# openmv.net
KiCad netlist of a schematic drawn in EAGLE
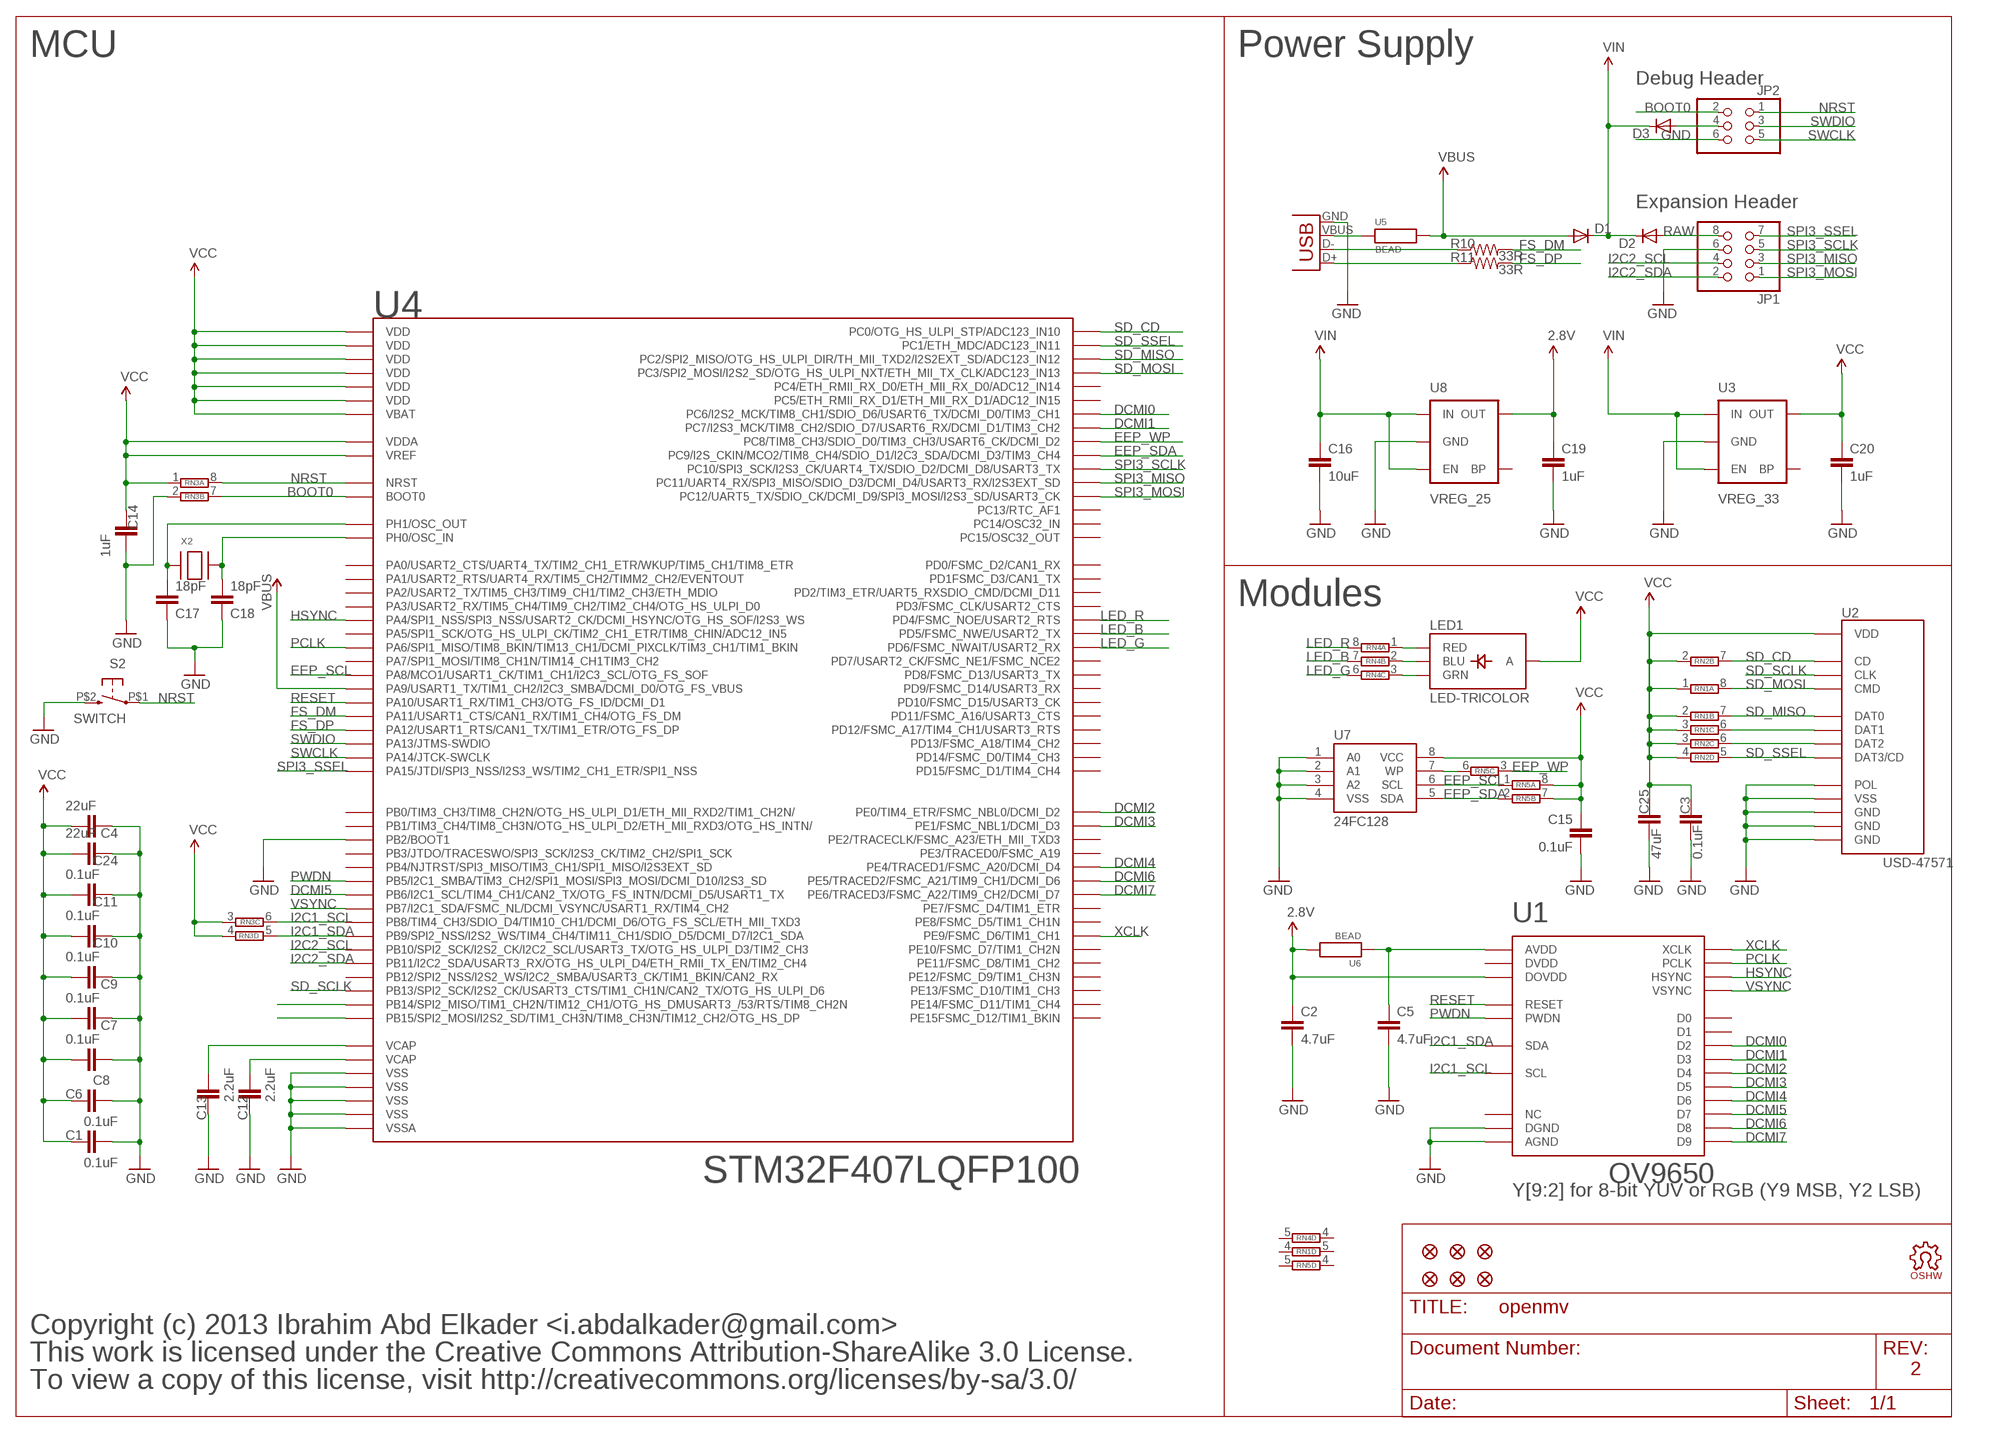
[diagram p0: schematic, sheet 1]

(export (version "E")
  (design (tool "Eeschema 10.0.6"))
  (components
    (comp (ref "C1")
      (value "0.1uF")
      (footprint "eagle-import:0402-CAP")
      (libsource (lib "eagle-import") (part "CAP0402-CAP"))
    )
    (comp (ref "C2")
      (value "4.7uF")
      (footprint "eagle-import:0402-CAP")
      (libsource (lib "eagle-import") (part "CAP0402-CAP"))
    )
    (comp (ref "C3")
      (value "0.1uF")
      (footprint "eagle-import:0402-CAP")
      (libsource (lib "eagle-import") (part "CAP0402-CAP"))
    )
    (comp (ref "C4")
      (value "22uF")
      (footprint "eagle-import:0805")
      (libsource (lib "eagle-import") (part "CAP0805"))
    )
    (comp (ref "C5")
      (value "4.7uF")
      (footprint "eagle-import:0402-CAP")
      (libsource (lib "eagle-import") (part "CAP0402-CAP"))
    )
    (comp (ref "C6")
      (value "0.1uF")
      (footprint "eagle-import:0402-CAP")
      (libsource (lib "eagle-import") (part "CAP0402-CAP"))
    )
    (comp (ref "C7")
      (value "0.1uF")
      (footprint "eagle-import:0402-CAP")
      (libsource (lib "eagle-import") (part "CAP0402-CAP"))
    )
    (comp (ref "C8")
      (value "0.1uF")
      (footprint "eagle-import:0402-CAP")
      (libsource (lib "eagle-import") (part "CAP0402-CAP"))
    )
    (comp (ref "C9")
      (value "0.1uF")
      (footprint "eagle-import:0402-CAP")
      (libsource (lib "eagle-import") (part "CAP0402-CAP"))
    )
    (comp (ref "C10")
      (value "0.1uF")
      (footprint "eagle-import:0402-CAP")
      (libsource (lib "eagle-import") (part "CAP0402-CAP"))
    )
    (comp (ref "C11")
      (value "0.1uF")
      (footprint "eagle-import:0402-CAP")
      (libsource (lib "eagle-import") (part "CAP0402-CAP"))
    )
    (comp (ref "C12")
      (value "2.2uF")
      (footprint "eagle-import:0402-CAP")
      (libsource (lib "eagle-import") (part "CAP0402-CAP"))
    )
    (comp (ref "C13")
      (value "2.2uF")
      (footprint "eagle-import:0402-CAP")
      (libsource (lib "eagle-import") (part "CAP0402-CAP"))
    )
    (comp (ref "C14")
      (value "1uF")
      (footprint "eagle-import:0402-CAP")
      (libsource (lib "eagle-import") (part "CAP0402-CAP"))
    )
    (comp (ref "C15")
      (value "0.1uF")
      (footprint "eagle-import:0402-CAP")
      (libsource (lib "eagle-import") (part "CAP0402-CAP"))
    )
    (comp (ref "C16")
      (value "10uF")
      (footprint "eagle-import:0805")
      (libsource (lib "eagle-import") (part "CAP0805"))
    )
    (comp (ref "C17")
      (value "18pF")
      (footprint "eagle-import:0402-CAP")
      (libsource (lib "eagle-import") (part "CAP0402-CAP"))
    )
    (comp (ref "C18")
      (value "18pF")
      (footprint "eagle-import:0402-CAP")
      (libsource (lib "eagle-import") (part "CAP0402-CAP"))
    )
    (comp (ref "C19")
      (value "1uF")
      (footprint "eagle-import:0402-CAP")
      (libsource (lib "eagle-import") (part "CAP0402-CAP"))
    )
    (comp (ref "C20")
      (value "1uF")
      (footprint "eagle-import:0402-CAP")
      (libsource (lib "eagle-import") (part "CAP0402-CAP"))
    )
    (comp (ref "C24")
      (value "22uF")
      (footprint "eagle-import:0805")
      (libsource (lib "eagle-import") (part "CAP0805"))
    )
    (comp (ref "C25")
      (value "47uF")
      (footprint "eagle-import:0805")
      (libsource (lib "eagle-import") (part "CAP0805"))
    )
    (comp (ref "D1")
      (value "DIODESOD")
      (footprint "eagle-import:SOD-323")
      (libsource (lib "eagle-import") (part "DIODESOD"))
    )
    (comp (ref "D2")
      (value "DIODESOD")
      (footprint "eagle-import:SOD-323")
      (libsource (lib "eagle-import") (part "DIODESOD"))
    )
    (comp (ref "D3")
      (value "DIODESOD")
      (footprint "eagle-import:SOD-323")
      (libsource (lib "eagle-import") (part "DIODESOD"))
    )
    (comp (ref "JP1")
      (value "PINHD-2X4")
      (footprint "eagle-import:2X04")
      (libsource (lib "eagle-import") (part "PINHD-2X4"))
    )
    (comp (ref "JP2")
      (value "PINHD-2X3")
      (footprint "eagle-import:2X03")
      (libsource (lib "eagle-import") (part "PINHD-2X3"))
    )
    (comp (ref "JP3")
      (value "FIDUCIAL1X2")
      (footprint "eagle-import:FIDUCIAL-1X2")
      (libsource (lib "eagle-import") (part "FIDUCIAL1X2"))
    )
    (comp (ref "JP4")
      (value "FIDUCIAL1X2")
      (footprint "eagle-import:FIDUCIAL-1X2")
      (libsource (lib "eagle-import") (part "FIDUCIAL1X2"))
    )
    (comp (ref "JP5")
      (value "FIDUCIAL1X2")
      (footprint "eagle-import:FIDUCIAL-1X2")
      (libsource (lib "eagle-import") (part "FIDUCIAL1X2"))
    )
    (comp (ref "JP6")
      (value "FIDUCIAL1X2")
      (footprint "eagle-import:FIDUCIAL-1X2")
      (libsource (lib "eagle-import") (part "FIDUCIAL1X2"))
    )
    (comp (ref "JP7")
      (value "FIDUCIAL1X2")
      (footprint "eagle-import:FIDUCIAL-1X2")
      (libsource (lib "eagle-import") (part "FIDUCIAL1X2"))
    )
    (comp (ref "JP8")
      (value "FIDUCIAL1X2")
      (footprint "eagle-import:FIDUCIAL-1X2")
      (libsource (lib "eagle-import") (part "FIDUCIAL1X2"))
    )
    (comp (ref "LED1")
      (value "LED-TRICOLOR")
      (footprint "eagle-import:LED-TRICOLOR-SMD")
      (libsource (lib "eagle-import") (part "LED-TRICOLOR"))
    )
    (comp (ref "LOGO1")
      (value "OSHW_LOGO_FILLX0150-NT")
      (footprint "eagle-import:OSHW_FILLX150_NOTEXT")
      (libsource (lib "eagle-import") (part "OSHW_LOGO_FILLX0150-NT"))
    )
    (comp (ref "R10")
      (value "33R")
      (footprint "eagle-import:0402-RES")
      (libsource (lib "eagle-import") (part "RESISTOR0402-RES"))
    )
    (comp (ref "R11")
      (value "33R")
      (footprint "eagle-import:0402-RES")
      (libsource (lib "eagle-import") (part "RESISTOR0402-RES"))
    )
    (comp (ref "RN1")
      (value "4R-NCAT16")
      (footprint "eagle-import:CAT16")
      (fields (field (name "OC_FARNELL") "unknown") (field (name "OC_NEWARK") "unknown"))
      (libsource (lib "eagle-import") (part "4R-NCAT16"))
    )
    (comp (ref "RN2")
      (value "4R-NCAT16")
      (footprint "eagle-import:CAT16")
      (fields (field (name "OC_FARNELL") "unknown") (field (name "OC_NEWARK") "unknown"))
      (libsource (lib "eagle-import") (part "4R-NCAT16"))
    )
    (comp (ref "RN3")
      (value "4R-NCAT16")
      (footprint "eagle-import:CAT16")
      (libsource (lib "eagle-import") (part "4R-NCAT16"))
    )
    (comp (ref "RN4")
      (value "4R-NCAT16")
      (footprint "eagle-import:CAT16")
      (fields (field (name "OC_FARNELL") "unknown") (field (name "OC_NEWARK") "unknown"))
      (libsource (lib "eagle-import") (part "4R-NCAT16"))
    )
    (comp (ref "RN5")
      (value "4R-NCAT16")
      (footprint "eagle-import:CAT16")
      (fields (field (name "OC_FARNELL") "unknown") (field (name "OC_NEWARK") "unknown"))
      (libsource (lib "eagle-import") (part "4R-NCAT16"))
    )
    (comp (ref "S2")
      (value "SWITCH")
      (footprint "eagle-import:B3U-1000P")
      (libsource (lib "eagle-import") (part "SWITCH"))
    )
    (comp (ref "U1")
      (value "OV9650")
      (footprint "eagle-import:OV9650")
      (libsource (lib "eagle-import") (part "OV9650"))
    )
    (comp (ref "U2")
      (value "USD-47571")
      (footprint "eagle-import:USD-47571")
      (libsource (lib "eagle-import") (part "USD-47571"))
    )
    (comp (ref "U3")
      (value "VREG_33")
      (footprint "eagle-import:SOT23-5")
      (libsource (lib "eagle-import") (part "V_REG_LDOSMD"))
    )
    (comp (ref "U4")
      (value "STM32F407LQFP100")
      (footprint "eagle-import:LQFP100")
      (libsource (lib "eagle-import") (part "STM32F407LQFP100"))
    )
    (comp (ref "U5")
      (value "BEAD")
      (footprint "eagle-import:0402-CAP")
      (libsource (lib "eagle-import") (part "BEAD"))
    )
    (comp (ref "U6")
      (value "BEAD")
      (footprint "eagle-import:0402-CAP")
      (libsource (lib "eagle-import") (part "BEAD"))
    )
    (comp (ref "U7")
      (value "24FC128")
      (footprint "eagle-import:MSOP8")
      (libsource (lib "eagle-import") (part "24FC128"))
    )
    (comp (ref "U8")
      (value "VREG_25")
      (footprint "eagle-import:SOT23-5")
      (libsource (lib "eagle-import") (part "V_REG_LDOSMD"))
    )
    (comp (ref "X1")
      (value "USB-MICROB")
      (footprint "eagle-import:USB-MICROB")
      (libsource (lib "eagle-import") (part "USB-MICROB"))
    )
    (comp (ref "X2")
      (value "XTALNX5032")
      (footprint "eagle-import:NX5032")
      (libsource (lib "eagle-import") (part "XTALNX5032"))
    )
  )
  (nets
    (net (code "1") (name "/BOOT0") (class "Default")
      (node (ref "JP2") (pin "2") (pinfunction "2_2") (pintype "passive"))
      (node (ref "RN3") (pin "7") (pinfunction "2_7") (pintype "passive"))
      (node (ref "U4") (pin "94") (pinfunction "BOOT0_94") (pintype "bidirectional"))
    )
    (net (code "2") (name "/DCMI0") (class "Default")
      (node (ref "U1") (pin "P$19") (pinfunction "D2_P$19") (pintype "bidirectional"))
      (node (ref "U4") (pin "63") (pinfunction "PC6/I2S2_MCK/TIM8_CH1/SDIO_D6/USART6_TX/DCMI_D0/TIM3_CH1_63") (pintype "bidirectional"))
    )
    (net (code "3") (name "/DCMI1") (class "Default")
      (node (ref "U1") (pin "P$21") (pinfunction "D3_P$21") (pintype "bidirectional"))
      (node (ref "U4") (pin "64") (pinfunction "PC7/I2S3_MCK/TIM8_CH2/SDIO_D7/USART6_RX/DCMI_D1/TIM3_CH2_64") (pintype "bidirectional"))
    )
    (net (code "4") (name "/DCMI2") (class "Default")
      (node (ref "U1") (pin "P$22") (pinfunction "D4_P$22") (pintype "bidirectional"))
      (node (ref "U4") (pin "97") (pinfunction "PE0/TIM4_ETR/FSMC_NBL0/DCMI_D2_97") (pintype "bidirectional"))
    )
    (net (code "5") (name "/DCMI3") (class "Default")
      (node (ref "U1") (pin "P$20") (pinfunction "D5_P$20") (pintype "bidirectional"))
      (node (ref "U4") (pin "98") (pinfunction "PE1/FSMC_NBL1/DCMI_D3_98") (pintype "bidirectional"))
    )
    (net (code "6") (name "/DCMI4") (class "Default")
      (node (ref "U1") (pin "P$18") (pinfunction "D6_P$18") (pintype "bidirectional"))
      (node (ref "U4") (pin "3") (pinfunction "PE4/TRACED1/FSMC_A20/DCMI_D4_3") (pintype "bidirectional"))
    )
    (net (code "7") (name "/DCMI5") (class "Default")
      (node (ref "U1") (pin "P$16") (pinfunction "D7_P$16") (pintype "bidirectional"))
      (node (ref "U4") (pin "92") (pinfunction "PB6/I2C1_SCL/TIM4_CH1/CAN2_TX/OTG_FS_INTN/DCMI_D5/USART1_TX_92") (pintype "bidirectional"))
    )
    (net (code "8") (name "/DCMI6") (class "Default")
      (node (ref "U1") (pin "P$14") (pinfunction "D8_P$14") (pintype "bidirectional"))
      (node (ref "U4") (pin "4") (pinfunction "PE5/TRACED2/FSMC_A21/TIM9_CH1/DCMI_D6_4") (pintype "bidirectional"))
    )
    (net (code "9") (name "/DCMI7") (class "Default")
      (node (ref "U1") (pin "P$12") (pinfunction "D9_P$12") (pintype "bidirectional"))
      (node (ref "U4") (pin "5") (pinfunction "PE6/TRACED3/FSMC_A22/TIM9_CH2/DCMI_D7_5") (pintype "bidirectional"))
    )
    (net (code "10") (name "/EEP_SCL") (class "Default")
      (node (ref "RN5") (pin "1") (pinfunction "1_1") (pintype "passive"))
      (node (ref "U4") (pin "67") (pinfunction "PA8/MCO1/USART1_CK/TIM1_CH1/I2C3_SCL/OTG_FS_SOF_67") (pintype "bidirectional"))
      (node (ref "U7") (pin "6") (pinfunction "SCL_6") (pintype "bidirectional"))
    )
    (net (code "11") (name "/EEP_SDA") (class "Default")
      (node (ref "RN5") (pin "2") (pinfunction "1_2") (pintype "passive"))
      (node (ref "U4") (pin "66") (pinfunction "PC9/I2S_CKIN/MCO2/TIM8_CH4/SDIO_D1/I2C3_SDA/DCMI_D3/TIM3_CH4_66") (pintype "bidirectional"))
      (node (ref "U7") (pin "5") (pinfunction "SDA_5") (pintype "bidirectional"))
    )
    (net (code "12") (name "/EEP_WP") (class "Default")
      (node (ref "RN5") (pin "3") (pinfunction "1_3") (pintype "passive"))
      (node (ref "U4") (pin "65") (pinfunction "PC8/TIM8_CH3/SDIO_D0/TIM3_CH3/USART6_CK/DCMI_D2_65") (pintype "bidirectional"))
    )
    (net (code "13") (name "/FS_DM") (class "Default")
      (node (ref "R10") (pin "2") (pinfunction "2_2") (pintype "passive"))
      (node (ref "U4") (pin "70") (pinfunction "PA11/USART1_CTS/CAN1_RX/TIM1_CH4/OTG_FS_DM_70") (pintype "bidirectional"))
    )
    (net (code "14") (name "/FS_DP") (class "Default")
      (node (ref "R11") (pin "2") (pinfunction "2_2") (pintype "passive"))
      (node (ref "U4") (pin "71") (pinfunction "PA12/USART1_RTS/CAN1_TX/TIM1_ETR/OTG_FS_DP_71") (pintype "bidirectional"))
    )
    (net (code "15") (name "/HSYNC") (class "Default")
      (node (ref "U1") (pin "P$9") (pinfunction "HSYNC_P$9") (pintype "bidirectional"))
      (node (ref "U4") (pin "29") (pinfunction "PA4/SPI1_NSS/SPI3_NSS/USART2_CK/DCMI_HSYNC/OTG_HS_SOF/I2S3_WS_29") (pintype "bidirectional"))
    )
    (net (code "16") (name "/I2C1_SCL") (class "Default")
      (node (ref "RN3") (pin "6") (pinfunction "2_6") (pintype "passive"))
      (node (ref "U1") (pin "P$5") (pinfunction "SCL_P$5") (pintype "bidirectional"))
      (node (ref "U4") (pin "95") (pinfunction "PB8/TIM4_CH3/SDIO_D4/TIM10_CH1/DCMI_D6/OTG_FS_SCL/ETH_MII_TXD3_95") (pintype "bidirectional"))
    )
    (net (code "17") (name "/I2C1_SDA") (class "Default")
      (node (ref "RN3") (pin "5") (pinfunction "2_5") (pintype "passive"))
      (node (ref "U1") (pin "P$3") (pinfunction "SDA_P$3") (pintype "bidirectional"))
      (node (ref "U4") (pin "96") (pinfunction "PB9/SPI2_NSS/I2S2_WS/TIM4_CH4/TIM11_CH1/SDIO_D5/DCMI_D7/I2C1_SDA_96") (pintype "bidirectional"))
    )
    (net (code "18") (name "/I2C2_SCL") (class "Default")
      (node (ref "JP1") (pin "4") (pinfunction "4_4") (pintype "passive"))
      (node (ref "U4") (pin "47") (pinfunction "PB10/SPI2_SCK/I2S2_CK/I2C2_SCL/USART3_TX/OTG_HS_ULPI_D3/TIM2_CH3_47") (pintype "bidirectional"))
    )
    (net (code "19") (name "/I2C2_SDA") (class "Default")
      (node (ref "JP1") (pin "2") (pinfunction "2_2") (pintype "passive"))
      (node (ref "U4") (pin "48") (pinfunction "PB11/I2C2_SDA/USART3_RX/OTG_HS_ULPI_D4/ETH_RMII_TX_EN/TIM2_CH4_48") (pintype "bidirectional"))
    )
    (net (code "20") (name "/LED_B") (class "Default")
      (node (ref "RN4") (pin "7") (pinfunction "2_7") (pintype "passive"))
      (node (ref "U4") (pin "86") (pinfunction "PD5/FSMC_NWE/USART2_TX_86") (pintype "bidirectional"))
    )
    (net (code "21") (name "/LED_G") (class "Default")
      (node (ref "RN4") (pin "6") (pinfunction "2_6") (pintype "passive"))
      (node (ref "U4") (pin "87") (pinfunction "PD6/FSMC_NWAIT/USART2_RX_87") (pintype "bidirectional"))
    )
    (net (code "22") (name "/LED_R") (class "Default")
      (node (ref "RN4") (pin "8") (pinfunction "2_8") (pintype "passive"))
      (node (ref "U4") (pin "85") (pinfunction "PD4/FSMC_NOE/USART2_RTS_85") (pintype "bidirectional"))
    )
    (net (code "23") (name "/NRST") (class "Default")
      (node (ref "JP2") (pin "1") (pinfunction "1_1") (pintype "passive"))
      (node (ref "RN3") (pin "8") (pinfunction "2_8") (pintype "passive"))
      (node (ref "S2") (pin "P$1") (pinfunction "1_P$1") (pintype "passive"))
      (node (ref "U4") (pin "14") (pinfunction "NRST_14") (pintype "bidirectional"))
    )
    (net (code "24") (name "/PCLK") (class "Default")
      (node (ref "U1") (pin "P$17") (pinfunction "PCLK_P$17") (pintype "bidirectional"))
      (node (ref "U4") (pin "31") (pinfunction "PA6/SPI1_MISO/TIM8_BKIN/TIM13_CH1/DCMI_PIXCLK/TIM3_CH1/TIM1_BKIN_31") (pintype "bidirectional"))
    )
    (net (code "25") (name "/PWDN") (class "Default")
      (node (ref "U1") (pin "P$8") (pinfunction "PWDN_P$8") (pintype "bidirectional"))
      (node (ref "U4") (pin "91") (pinfunction "PB5/I2C1_SMBA/TIM3_CH2/SPI1_MOSI/SPI3_MOSI/DCMI_D10/I2S3_SD_91") (pintype "bidirectional"))
    )
    (net (code "26") (name "/RAW") (class "Default")
      (node (ref "D2") (pin "2") (pinfunction "A_2") (pintype "passive"))
      (node (ref "JP1") (pin "8") (pinfunction "8_8") (pintype "passive"))
    )
    (net (code "27") (name "/RESET") (class "Default")
      (node (ref "U1") (pin "P$6") (pinfunction "RESET_P$6") (pintype "bidirectional"))
      (node (ref "U4") (pin "69") (pinfunction "PA10/USART1_RX/TIM1_CH3/OTG_FS_ID/DCMI_D1_69") (pintype "bidirectional"))
    )
    (net (code "28") (name "/SD_CD") (class "Default")
      (node (ref "RN2") (pin "7") (pinfunction "2_7") (pintype "passive"))
      (node (ref "U2") (pin "G$5") (pinfunction "CD_G$5") (pintype "power_in"))
      (node (ref "U4") (pin "15") (pinfunction "PC0/OTG_HS_ULPI_STP/ADC123_IN10_15") (pintype "bidirectional"))
    )
    (net (code "29") (name "/SD_MISO") (class "Default")
      (node (ref "RN1") (pin "7") (pinfunction "2_7") (pintype "passive"))
      (node (ref "U2") (pin "P$7") (pinfunction "DAT0_P$7") (pintype "bidirectional"))
      (node (ref "U4") (pin "17") (pinfunction "PC2/SPI2_MISO/OTG_HS_ULPI_DIR/TH_MII_TXD2/I2S2EXT_SD/ADC123_IN12_17") (pintype "bidirectional"))
    )
    (net (code "30") (name "/SD_MOSI") (class "Default")
      (node (ref "RN1") (pin "8") (pinfunction "2_8") (pintype "passive"))
      (node (ref "U2") (pin "P$3") (pinfunction "CMD_P$3") (pintype "bidirectional"))
      (node (ref "U4") (pin "18") (pinfunction "PC3/SPI2_MOSI/I2S2_SD/OTG_HS_ULPI_NXT/ETH_MII_TX_CLK/ADC123_IN13_18") (pintype "bidirectional"))
    )
    (net (code "31") (name "/SD_SCLK") (class "Default")
      (node (ref "U2") (pin "P$5") (pinfunction "CLK_P$5") (pintype "bidirectional"))
      (node (ref "U4") (pin "52") (pinfunction "PB13/SPI2_SCK/I2S2_CK/USART3_CTS/TIM1_CH1N/CAN2_TX/OTG_HS_ULPI_D6_52") (pintype "bidirectional"))
    )
    (net (code "32") (name "/SD_SSEL") (class "Default")
      (node (ref "RN2") (pin "5") (pinfunction "2_5") (pintype "passive"))
      (node (ref "U2") (pin "P$2") (pinfunction "DAT3/CD_P$2") (pintype "bidirectional"))
      (node (ref "U4") (pin "16") (pinfunction "PC1/ETH_MDC/ADC123_IN11_16") (pintype "bidirectional"))
    )
    (net (code "33") (name "/SPI3_MISO") (class "Default")
      (node (ref "JP1") (pin "3") (pinfunction "3_3") (pintype "passive"))
      (node (ref "U4") (pin "79") (pinfunction "PC11/UART4_RX/SPI3_MISO/SDIO_D3/DCMI_D4/USART3_RX/I2S3EXT_SD_79") (pintype "bidirectional"))
    )
    (net (code "34") (name "/SPI3_MOSI") (class "Default")
      (node (ref "JP1") (pin "1") (pinfunction "1_1") (pintype "passive"))
      (node (ref "U4") (pin "80") (pinfunction "PC12/UART5_TX/SDIO_CK/DCMI_D9/SPI3_MOSI/I2S3_SD/USART3_CK_80") (pintype "bidirectional"))
    )
    (net (code "35") (name "/SPI3_SCLK") (class "Default")
      (node (ref "JP1") (pin "5") (pinfunction "5_5") (pintype "passive"))
      (node (ref "U4") (pin "78") (pinfunction "PC10/SPI3_SCK/I2S3_CK/UART4_TX/SDIO_D2/DCMI_D8/USART3_TX_78") (pintype "bidirectional"))
    )
    (net (code "36") (name "/SPI3_SSEL") (class "Default")
      (node (ref "JP1") (pin "7") (pinfunction "7_7") (pintype "passive"))
      (node (ref "U4") (pin "77") (pinfunction "PA15/JTDI/SPI3_NSS/I2S3_WS/TIM2_CH1_ETR/SPI1_NSS_77") (pintype "bidirectional"))
    )
    (net (code "37") (name "/SWCLK") (class "Default")
      (node (ref "JP2") (pin "5") (pinfunction "5_5") (pintype "passive"))
      (node (ref "U4") (pin "76") (pinfunction "PA14/JTCK-SWCLK_76") (pintype "bidirectional"))
    )
    (net (code "38") (name "/SWDIO") (class "Default")
      (node (ref "JP2") (pin "3") (pinfunction "3_3") (pintype "passive"))
      (node (ref "U4") (pin "72") (pinfunction "PA13/JTMS-SWDIO_72") (pintype "bidirectional"))
    )
    (net (code "39") (name "/VSYNC") (class "Default")
      (node (ref "U1") (pin "P$7") (pinfunction "VSYNC_P$7") (pintype "bidirectional"))
      (node (ref "U4") (pin "93") (pinfunction "PB7/I2C1_SDA/FSMC_NL/DCMI_VSYNC/USART1_RX/TIM4_CH2_93") (pintype "bidirectional"))
    )
    (net (code "40") (name "/XCLK") (class "Default")
      (node (ref "U1") (pin "P$13") (pinfunction "XCLK_P$13") (pintype "bidirectional"))
      (node (ref "U4") (pin "40") (pinfunction "PE9/FSMC_D6/TIM1_CH1_40") (pintype "bidirectional"))
    )
    (net (code "41") (name "2.8V") (class "Default")
      (node (ref "C19") (pin "1") (pinfunction "1_1") (pintype "passive"))
      (node (ref "C2") (pin "1") (pinfunction "1_1") (pintype "passive"))
      (node (ref "U1") (pin "P$11") (pinfunction "DOVDD_P$11") (pintype "bidirectional"))
      (node (ref "U6") (pin "2") (pinfunction "2_2") (pintype "passive"))
      (node (ref "U8") (pin "5") (pinfunction "OUT_5") (pintype "passive"))
    )
    (net (code "42") (name "GND") (class "Default")
      (node (ref "C1") (pin "1") (pinfunction "1_1") (pintype "passive"))
      (node (ref "C10") (pin "2") (pinfunction "2_2") (pintype "passive"))
      (node (ref "C11") (pin "2") (pinfunction "2_2") (pintype "passive"))
      (node (ref "C12") (pin "2") (pinfunction "2_2") (pintype "passive"))
      (node (ref "C13") (pin "2") (pinfunction "2_2") (pintype "passive"))
      (node (ref "C14") (pin "1") (pinfunction "1_1") (pintype "passive"))
      (node (ref "C15") (pin "2") (pinfunction "2_2") (pintype "passive"))
      (node (ref "C16") (pin "2") (pinfunction "2_2") (pintype "passive"))
      (node (ref "C17") (pin "1") (pinfunction "1_1") (pintype "passive"))
      (node (ref "C18") (pin "1") (pinfunction "1_1") (pintype "passive"))
      (node (ref "C19") (pin "2") (pinfunction "2_2") (pintype "passive"))
      (node (ref "C2") (pin "2") (pinfunction "2_2") (pintype "passive"))
      (node (ref "C20") (pin "2") (pinfunction "2_2") (pintype "passive"))
      (node (ref "C24") (pin "1") (pinfunction "1_1") (pintype "passive"))
      (node (ref "C25") (pin "2") (pinfunction "2_2") (pintype "passive"))
      (node (ref "C3") (pin "2") (pinfunction "2_2") (pintype "passive"))
      (node (ref "C4") (pin "1") (pinfunction "1_1") (pintype "passive"))
      (node (ref "C5") (pin "2") (pinfunction "2_2") (pintype "passive"))
      (node (ref "C6") (pin "1") (pinfunction "1_1") (pintype "passive"))
      (node (ref "C7") (pin "2") (pinfunction "2_2") (pintype "passive"))
      (node (ref "C8") (pin "1") (pinfunction "1_1") (pintype "passive"))
      (node (ref "C9") (pin "2") (pinfunction "2_2") (pintype "passive"))
      (node (ref "JP1") (pin "6") (pinfunction "6_6") (pintype "passive"))
      (node (ref "JP2") (pin "6") (pinfunction "6_6") (pintype "passive"))
      (node (ref "RN3") (pin "2") (pinfunction "1_2") (pintype "passive"))
      (node (ref "S2") (pin "P$2") (pinfunction "2_P$2") (pintype "passive"))
      (node (ref "U1") (pin "P$15") (pinfunction "DGND_P$15") (pintype "bidirectional"))
      (node (ref "U1") (pin "P$2") (pinfunction "AGND_P$2") (pintype "power_in"))
      (node (ref "U2") (pin "G$1") (pinfunction "GND_G$1") (pintype "power_in"))
      (node (ref "U2") (pin "G$2") (pinfunction "GND_G$2") (pintype "power_in"))
      (node (ref "U2") (pin "G$3") (pinfunction "GND_G$3") (pintype "power_in"))
      (node (ref "U2") (pin "G$4") (pinfunction "POL_G$4") (pintype "power_in"))
      (node (ref "U2") (pin "P$6") (pinfunction "VSS_P$6") (pintype "power_in"))
      (node (ref "U3") (pin "2") (pinfunction "GND_2") (pintype "input"))
      (node (ref "U4") (pin "10") (pinfunction "VSS_10") (pintype "power_in"))
      (node (ref "U4") (pin "20") (pinfunction "VSSA_20") (pintype "power_in"))
      (node (ref "U4") (pin "27") (pinfunction "VSS_27") (pintype "power_in"))
      (node (ref "U4") (pin "37") (pinfunction "PB2/BOOT1_37") (pintype "bidirectional"))
      (node (ref "U4") (pin "74") (pinfunction "VSS_74") (pintype "power_in"))
      (node (ref "U4") (pin "99") (pinfunction "VSS_99") (pintype "power_in"))
      (node (ref "U7") (pin "1") (pinfunction "A0_1") (pintype "bidirectional"))
      (node (ref "U7") (pin "2") (pinfunction "A1_2") (pintype "bidirectional"))
      (node (ref "U7") (pin "3") (pinfunction "A2_3") (pintype "bidirectional"))
      (node (ref "U7") (pin "4") (pinfunction "VSS_4") (pintype "power_in"))
      (node (ref "U8") (pin "2") (pinfunction "GND_2") (pintype "input"))
      (node (ref "X1") (pin "GND") (pinfunction "GND_GND") (pintype "bidirectional"))
    )
    (net (code "43") (name "Net-(C12-Pad1)") (class "Default")
      (node (ref "C12") (pin "1") (pinfunction "1_1") (pintype "passive"))
      (node (ref "U4") (pin "73") (pinfunction "VCAP_73") (pintype "power_in"))
    )
    (net (code "44") (name "Net-(C13-Pad1)") (class "Default")
      (node (ref "C13") (pin "1") (pinfunction "1_1") (pintype "passive"))
      (node (ref "U4") (pin "49") (pinfunction "VCAP_49") (pintype "power_in"))
    )
    (net (code "45") (name "Net-(D3-A)") (class "Default")
      (node (ref "D3") (pin "2") (pinfunction "A_2") (pintype "passive"))
      (node (ref "JP2") (pin "4") (pinfunction "4_4") (pintype "passive"))
    )
    (net (code "46") (name "Net-(LED1-BLU)") (class "Default")
      (node (ref "LED1") (pin "B") (pinfunction "BLU_B") (pintype "bidirectional"))
      (node (ref "RN4") (pin "2") (pinfunction "1_2") (pintype "passive"))
    )
    (net (code "47") (name "Net-(LED1-GRN)") (class "Default")
      (node (ref "LED1") (pin "G") (pinfunction "GRN_G") (pintype "bidirectional"))
      (node (ref "RN4") (pin "3") (pinfunction "1_3") (pintype "passive"))
    )
    (net (code "48") (name "Net-(LED1-RED)") (class "Default")
      (node (ref "LED1") (pin "R") (pinfunction "RED_R") (pintype "bidirectional"))
      (node (ref "RN4") (pin "1") (pinfunction "1_1") (pintype "passive"))
    )
    (net (code "49") (name "Net-(R10-Pad1)") (class "Default")
      (node (ref "R10") (pin "1") (pinfunction "1_1") (pintype "passive"))
      (node (ref "X1") (pin "D-") (pinfunction "D-_D-") (pintype "bidirectional"))
    )
    (net (code "50") (name "Net-(R11-Pad1)") (class "Default")
      (node (ref "R11") (pin "1") (pinfunction "1_1") (pintype "passive"))
      (node (ref "X1") (pin "D+") (pinfunction "D+_D+") (pintype "bidirectional"))
    )
    (net (code "51") (name "Net-(RN1C-2)") (class "Default")
      (node (ref "RN1") (pin "6") (pinfunction "2_6") (pintype "passive"))
      (node (ref "U2") (pin "P$8") (pinfunction "DAT1_P$8") (pintype "bidirectional"))
    )
    (net (code "52") (name "Net-(RN2C-2)") (class "Default")
      (node (ref "RN2") (pin "6") (pinfunction "2_6") (pintype "passive"))
      (node (ref "U2") (pin "P$1") (pinfunction "DAT2_P$1") (pintype "bidirectional"))
    )
    (net (code "53") (name "Net-(RN5C-2)") (class "Default")
      (node (ref "RN5") (pin "6") (pinfunction "2_6") (pintype "passive"))
      (node (ref "U7") (pin "7") (pinfunction "WP_7") (pintype "bidirectional"))
    )
    (net (code "54") (name "Net-(U1-AVDD)") (class "Default")
      (node (ref "C5") (pin "1") (pinfunction "1_1") (pintype "passive"))
      (node (ref "U1") (pin "P$4") (pinfunction "AVDD_P$4") (pintype "power_in"))
      (node (ref "U6") (pin "1") (pinfunction "1_1") (pintype "passive"))
    )
    (net (code "55") (name "Net-(U4-PH0{slash}OSC_IN)") (class "Default")
      (node (ref "C18") (pin "2") (pinfunction "2_2") (pintype "passive"))
      (node (ref "U4") (pin "12") (pinfunction "PH0/OSC_IN_12") (pintype "bidirectional"))
      (node (ref "X2") (pin "P$2") (pinfunction "P$2_P$2") (pintype "bidirectional"))
    )
    (net (code "56") (name "Net-(U4-PH1{slash}OSC_OUT)") (class "Default")
      (node (ref "C17") (pin "2") (pinfunction "2_2") (pintype "passive"))
      (node (ref "U4") (pin "13") (pinfunction "PH1/OSC_OUT_13") (pintype "bidirectional"))
      (node (ref "X2") (pin "P$1") (pinfunction "P$1_P$1") (pintype "bidirectional"))
    )
    (net (code "57") (name "Net-(U5-Pad1)") (class "Default")
      (node (ref "U5") (pin "1") (pinfunction "1_1") (pintype "passive"))
      (node (ref "X1") (pin "VBUS") (pinfunction "VBUS_VBUS") (pintype "bidirectional"))
    )
    (net (code "58") (name "VBUS") (class "Default")
      (node (ref "D1") (pin "2") (pinfunction "A_2") (pintype "passive"))
      (node (ref "U4") (pin "68") (pinfunction "PA9/USART1_TX/TIM1_CH2/I2C3_SMBA/DCMI_D0/OTG_FS_VBUS_68") (pintype "bidirectional"))
      (node (ref "U5") (pin "2") (pinfunction "2_2") (pintype "passive"))
    )
    (net (code "59") (name "VCC") (class "Default")
      (node (ref "C1") (pin "2") (pinfunction "2_2") (pintype "passive"))
      (node (ref "C10") (pin "1") (pinfunction "1_1") (pintype "passive"))
      (node (ref "C11") (pin "1") (pinfunction "1_1") (pintype "passive"))
      (node (ref "C14") (pin "2") (pinfunction "2_2") (pintype "passive"))
      (node (ref "C15") (pin "1") (pinfunction "1_1") (pintype "passive"))
      (node (ref "C20") (pin "1") (pinfunction "1_1") (pintype "passive"))
      (node (ref "C24") (pin "2") (pinfunction "2_2") (pintype "passive"))
      (node (ref "C25") (pin "1") (pinfunction "1_1") (pintype "passive"))
      (node (ref "C3") (pin "1") (pinfunction "1_1") (pintype "passive"))
      (node (ref "C4") (pin "2") (pinfunction "2_2") (pintype "passive"))
      (node (ref "C6") (pin "2") (pinfunction "2_2") (pintype "passive"))
      (node (ref "C7") (pin "1") (pinfunction "1_1") (pintype "passive"))
      (node (ref "C8") (pin "2") (pinfunction "2_2") (pintype "passive"))
      (node (ref "C9") (pin "1") (pinfunction "1_1") (pintype "passive"))
      (node (ref "LED1") (pin "A") (pinfunction "A_A") (pintype "bidirectional"))
      (node (ref "RN1") (pin "1") (pinfunction "1_1") (pintype "passive"))
      (node (ref "RN1") (pin "2") (pinfunction "1_2") (pintype "passive"))
      (node (ref "RN1") (pin "3") (pinfunction "1_3") (pintype "passive"))
      (node (ref "RN2") (pin "2") (pinfunction "1_2") (pintype "passive"))
      (node (ref "RN2") (pin "3") (pinfunction "1_3") (pintype "passive"))
      (node (ref "RN2") (pin "4") (pinfunction "1_4") (pintype "passive"))
      (node (ref "RN3") (pin "1") (pinfunction "1_1") (pintype "passive"))
      (node (ref "RN3") (pin "3") (pinfunction "1_3") (pintype "passive"))
      (node (ref "RN3") (pin "4") (pinfunction "1_4") (pintype "passive"))
      (node (ref "RN5") (pin "7") (pinfunction "2_7") (pintype "passive"))
      (node (ref "RN5") (pin "8") (pinfunction "2_8") (pintype "passive"))
      (node (ref "U2") (pin "P$4") (pinfunction "VDD_P$4") (pintype "power_in"))
      (node (ref "U3") (pin "5") (pinfunction "OUT_5") (pintype "passive"))
      (node (ref "U4") (pin "100") (pinfunction "VDD_100") (pintype "power_in"))
      (node (ref "U4") (pin "11") (pinfunction "VDD_11") (pintype "power_in"))
      (node (ref "U4") (pin "19") (pinfunction "VDD_19") (pintype "power_in"))
      (node (ref "U4") (pin "21") (pinfunction "VREF_21") (pintype "power_in"))
      (node (ref "U4") (pin "22") (pinfunction "VDDA_22") (pintype "power_in"))
      (node (ref "U4") (pin "28") (pinfunction "VDD_28") (pintype "power_in"))
      (node (ref "U4") (pin "50") (pinfunction "VDD_50") (pintype "power_in"))
      (node (ref "U4") (pin "6") (pinfunction "VBAT_6") (pintype "power_in"))
      (node (ref "U4") (pin "75") (pinfunction "VDD_75") (pintype "power_in"))
      (node (ref "U7") (pin "8") (pinfunction "VCC_8") (pintype "power_in"))
    )
    (net (code "60") (name "VIN") (class "Default")
      (node (ref "C16") (pin "1") (pinfunction "1_1") (pintype "passive"))
      (node (ref "D1") (pin "1") (pinfunction "C_1") (pintype "passive"))
      (node (ref "D2") (pin "1") (pinfunction "C_1") (pintype "passive"))
      (node (ref "D3") (pin "1") (pinfunction "C_1") (pintype "passive"))
      (node (ref "U3") (pin "1") (pinfunction "IN_1") (pintype "input"))
      (node (ref "U3") (pin "3") (pinfunction "EN_3") (pintype "input"))
      (node (ref "U8") (pin "1") (pinfunction "IN_1") (pintype "input"))
      (node (ref "U8") (pin "3") (pinfunction "EN_3") (pintype "input"))
    )
    (net (code "61") (name "unconnected-(RN1D-1-Pad4)") (class "Default")
      (node (ref "RN1") (pin "4") (pinfunction "1_4") (pintype "passive"))
    )
    (net (code "62") (name "unconnected-(RN1D-2-Pad5)") (class "Default")
      (node (ref "RN1") (pin "5") (pinfunction "2_5") (pintype "passive"))
    )
    (net (code "63") (name "unconnected-(RN4D-1-Pad4)") (class "Default")
      (node (ref "RN4") (pin "4") (pinfunction "1_4") (pintype "passive"))
    )
    (net (code "64") (name "unconnected-(RN4D-2-Pad5)") (class "Default")
      (node (ref "RN4") (pin "5") (pinfunction "2_5") (pintype "passive"))
    )
    (net (code "65") (name "unconnected-(RN5D-1-Pad4)") (class "Default")
      (node (ref "RN5") (pin "4") (pinfunction "1_4") (pintype "passive"))
    )
    (net (code "66") (name "unconnected-(RN5D-2-Pad5)") (class "Default")
      (node (ref "RN5") (pin "5") (pinfunction "2_5") (pintype "passive"))
    )
    (net (code "67") (name "unconnected-(U1-D0-PadP$24)") (class "Default")
      (node (ref "U1") (pin "P$24") (pinfunction "D0_P$24") (pintype "bidirectional"))
    )
    (net (code "68") (name "unconnected-(U1-D1-PadP$23)") (class "Default")
      (node (ref "U1") (pin "P$23") (pinfunction "D1_P$23") (pintype "bidirectional"))
    )
    (net (code "69") (name "unconnected-(U1-DVDD-PadP$10)") (class "Default")
      (node (ref "U1") (pin "P$10") (pinfunction "DVDD_P$10") (pintype "bidirectional"))
    )
    (net (code "70") (name "unconnected-(U1-NC-PadP$1)") (class "Default")
      (node (ref "U1") (pin "P$1") (pinfunction "NC_P$1") (pintype "no_connect"))
    )
    (net (code "71") (name "unconnected-(U3-BP-Pad4)") (class "Default")
      (node (ref "U3") (pin "4") (pinfunction "BP_4") (pintype "input"))
    )
    (net (code "72") (name "unconnected-(U4-PA0{slash}USART2_CTS{slash}UART4_TX{slash}TIM2_CH1_ETR{slash}WKUP{slash}TIM5_CH1{slash}TIM8_ETR-Pad23)") (class "Default")
      (node (ref "U4") (pin "23") (pinfunction "PA0/USART2_CTS/UART4_TX/TIM2_CH1_ETR/WKUP/TIM5_CH1/TIM8_ETR_23") (pintype "bidirectional"))
    )
    (net (code "73") (name "unconnected-(U4-PA1{slash}USART2_RTS{slash}UART4_RX{slash}TIM5_CH2{slash}TIMM2_CH2{slash}EVENTOUT-Pad24)") (class "Default")
      (node (ref "U4") (pin "24") (pinfunction "PA1/USART2_RTS/UART4_RX/TIM5_CH2/TIMM2_CH2/EVENTOUT_24") (pintype "bidirectional"))
    )
    (net (code "74") (name "unconnected-(U4-PA2{slash}USART2_TX{slash}TIM5_CH3{slash}TIM9_CH1{slash}TIM2_CH3{slash}ETH_MDIO-Pad25)") (class "Default")
      (node (ref "U4") (pin "25") (pinfunction "PA2/USART2_TX/TIM5_CH3/TIM9_CH1/TIM2_CH3/ETH_MDIO_25") (pintype "bidirectional"))
    )
    (net (code "75") (name "unconnected-(U4-PA3{slash}USART2_RX{slash}TIM5_CH4{slash}TIM9_CH2{slash}TIM2_CH4{slash}OTG_HS_ULPI_D0-Pad26)") (class "Default")
      (node (ref "U4") (pin "26") (pinfunction "PA3/USART2_RX/TIM5_CH4/TIM9_CH2/TIM2_CH4/OTG_HS_ULPI_D0_26") (pintype "bidirectional"))
    )
    (net (code "76") (name "unconnected-(U4-PA5{slash}SPI1_SCK{slash}OTG_HS_ULPI_CK{slash}TIM2_CH1_ETR{slash}TIM8_CHIN{slash}ADC12_IN5-Pad30)") (class "Default")
      (node (ref "U4") (pin "30") (pinfunction "PA5/SPI1_SCK/OTG_HS_ULPI_CK/TIM2_CH1_ETR/TIM8_CHIN/ADC12_IN5_30") (pintype "bidirectional"))
    )
    (net (code "77") (name "unconnected-(U4-PA7{slash}SPI1_MOSI{slash}TIM8_CH1N{slash}TIM14_CH1TIM3_CH2-Pad32)") (class "Default")
      (node (ref "U4") (pin "32") (pinfunction "PA7/SPI1_MOSI/TIM8_CH1N/TIM14_CH1TIM3_CH2_32") (pintype "bidirectional"))
    )
    (net (code "78") (name "unconnected-(U4-PB0{slash}TIM3_CH3{slash}TIM8_CH2N{slash}OTG_HS_ULPI_D1{slash}ETH_MII_RXD2{slash}TIM1_CH2N{slash}-Pad35)") (class "Default")
      (node (ref "U4") (pin "35") (pinfunction "PB0/TIM3_CH3/TIM8_CH2N/OTG_HS_ULPI_D1/ETH_MII_RXD2/TIM1_CH2N/_35") (pintype "bidirectional"))
    )
    (net (code "79") (name "unconnected-(U4-PB1{slash}TIM3_CH4{slash}TIM8_CH3N{slash}OTG_HS_ULPI_D2{slash}ETH_MII_RXD3{slash}OTG_HS_INTN{slash}-Pad36)") (class "Default")
      (node (ref "U4") (pin "36") (pinfunction "PB1/TIM3_CH4/TIM8_CH3N/OTG_HS_ULPI_D2/ETH_MII_RXD3/OTG_HS_INTN/_36") (pintype "bidirectional"))
    )
    (net (code "80") (name "unconnected-(U4-PB3{slash}JTDO{slash}TRACESWO{slash}SPI3_SCK{slash}I2S3_CK{slash}TIM2_CH2{slash}SPI1_SCK-Pad89)") (class "Default")
      (node (ref "U4") (pin "89") (pinfunction "PB3/JTDO/TRACESWO/SPI3_SCK/I2S3_CK/TIM2_CH2/SPI1_SCK_89") (pintype "bidirectional"))
    )
    (net (code "81") (name "unconnected-(U4-PB4{slash}NJTRST{slash}SPI3_MISO{slash}TIM3_CH1{slash}SPI1_MISO{slash}I2S3EXT_SD-Pad90)") (class "Default")
      (node (ref "U4") (pin "90") (pinfunction "PB4/NJTRST/SPI3_MISO/TIM3_CH1/SPI1_MISO/I2S3EXT_SD_90") (pintype "bidirectional"))
    )
    (net (code "82") (name "unconnected-(U4-PB12{slash}SPI2_NSS{slash}I2S2_WS{slash}I2C2_SMBA{slash}USART3_CK{slash}TIM1_BKIN{slash}CAN2_RX-Pad51)") (class "Default")
      (node (ref "U4") (pin "51") (pinfunction "PB12/SPI2_NSS/I2S2_WS/I2C2_SMBA/USART3_CK/TIM1_BKIN/CAN2_RX_51") (pintype "bidirectional"))
    )
    (net (code "83") (name "unconnected-(U4-PB14{slash}SPI2_MISO{slash}TIM1_CH2N{slash}TIM12_CH1{slash}OTG_HS_DMUSART3_{slash}53{slash}RTS{slash}TIM8_CH2N-Pad53)") (class "Default")
      (node (ref "U4") (pin "53") (pinfunction "PB14/SPI2_MISO/TIM1_CH2N/TIM12_CH1/OTG_HS_DMUSART3_/53/RTS/TIM8_CH2N_53") (pintype "bidirectional"))
    )
    (net (code "84") (name "unconnected-(U4-PB15{slash}SPI2_MOSI{slash}I2S2_SD{slash}TIM1_CH3N{slash}TIM8_CH3N{slash}TIM12_CH2{slash}OTG_HS_DP-Pad54)") (class "Default")
      (node (ref "U4") (pin "54") (pinfunction "PB15/SPI2_MOSI/I2S2_SD/TIM1_CH3N/TIM8_CH3N/TIM12_CH2/OTG_HS_DP_54") (pintype "bidirectional"))
    )
    (net (code "85") (name "unconnected-(U4-PC4{slash}ETH_RMII_RX_D0{slash}ETH_MII_RX_D0{slash}ADC12_IN14-Pad33)") (class "Default")
      (node (ref "U4") (pin "33") (pinfunction "PC4/ETH_RMII_RX_D0/ETH_MII_RX_D0/ADC12_IN14_33") (pintype "bidirectional"))
    )
    (net (code "86") (name "unconnected-(U4-PC5{slash}ETH_RMII_RX_D1{slash}ETH_MII_RX_D1{slash}ADC12_IN15-Pad34)") (class "Default")
      (node (ref "U4") (pin "34") (pinfunction "PC5/ETH_RMII_RX_D1/ETH_MII_RX_D1/ADC12_IN15_34") (pintype "bidirectional"))
    )
    (net (code "87") (name "unconnected-(U4-PC13{slash}RTC_AF1-Pad7)") (class "Default")
      (node (ref "U4") (pin "7") (pinfunction "PC13/RTC_AF1_7") (pintype "bidirectional"))
    )
    (net (code "88") (name "unconnected-(U4-PC14{slash}OSC32_IN-Pad8)") (class "Default")
      (node (ref "U4") (pin "8") (pinfunction "PC14/OSC32_IN_8") (pintype "bidirectional"))
    )
    (net (code "89") (name "unconnected-(U4-PC15{slash}OSC32_OUT-Pad9)") (class "Default")
      (node (ref "U4") (pin "9") (pinfunction "PC15/OSC32_OUT_9") (pintype "bidirectional"))
    )
    (net (code "90") (name "unconnected-(U4-PD0{slash}FSMC_D2{slash}CAN1_RX-Pad81)") (class "Default")
      (node (ref "U4") (pin "81") (pinfunction "PD0/FSMC_D2/CAN1_RX_81") (pintype "bidirectional"))
    )
    (net (code "91") (name "unconnected-(U4-PD1FSMC_D3{slash}CAN1_TX-Pad82)") (class "Default")
      (node (ref "U4") (pin "82") (pinfunction "PD1FSMC_D3/CAN1_TX_82") (pintype "bidirectional"))
    )
    (net (code "92") (name "unconnected-(U4-PD2{slash}TIM3_ETR{slash}UART5_RXSDIO_CMD{slash}DCMI_D11-Pad83)") (class "Default")
      (node (ref "U4") (pin "83") (pinfunction "PD2/TIM3_ETR/UART5_RXSDIO_CMD/DCMI_D11_83") (pintype "bidirectional"))
    )
    (net (code "93") (name "unconnected-(U4-PD3{slash}FSMC_CLK{slash}USART2_CTS-Pad84)") (class "Default")
      (node (ref "U4") (pin "84") (pinfunction "PD3/FSMC_CLK/USART2_CTS_84") (pintype "bidirectional"))
    )
    (net (code "94") (name "unconnected-(U4-PD7{slash}USART2_CK{slash}FSMC_NE1{slash}FSMC_NCE2-Pad88)") (class "Default")
      (node (ref "U4") (pin "88") (pinfunction "PD7/USART2_CK/FSMC_NE1/FSMC_NCE2_88") (pintype "bidirectional"))
    )
    (net (code "95") (name "unconnected-(U4-PD8{slash}FSMC_D13{slash}USART3_TX-Pad55)") (class "Default")
      (node (ref "U4") (pin "55") (pinfunction "PD8/FSMC_D13/USART3_TX_55") (pintype "bidirectional"))
    )
    (net (code "96") (name "unconnected-(U4-PD9{slash}FSMC_D14{slash}USART3_RX-Pad56)") (class "Default")
      (node (ref "U4") (pin "56") (pinfunction "PD9/FSMC_D14/USART3_RX_56") (pintype "bidirectional"))
    )
    (net (code "97") (name "unconnected-(U4-PD10{slash}FSMC_D15{slash}USART3_CK-Pad57)") (class "Default")
      (node (ref "U4") (pin "57") (pinfunction "PD10/FSMC_D15/USART3_CK_57") (pintype "bidirectional"))
    )
    (net (code "98") (name "unconnected-(U4-PD11{slash}FSMC_A16{slash}USART3_CTS-Pad58)") (class "Default")
      (node (ref "U4") (pin "58") (pinfunction "PD11/FSMC_A16/USART3_CTS_58") (pintype "bidirectional"))
    )
    (net (code "99") (name "unconnected-(U4-PD12{slash}FSMC_A17{slash}TIM4_CH1{slash}USART3_RTS-Pad59)") (class "Default")
      (node (ref "U4") (pin "59") (pinfunction "PD12/FSMC_A17/TIM4_CH1/USART3_RTS_59") (pintype "bidirectional"))
    )
    (net (code "100") (name "unconnected-(U4-PD13{slash}FSMC_A18{slash}TIM4_CH2-Pad60)") (class "Default")
      (node (ref "U4") (pin "60") (pinfunction "PD13/FSMC_A18/TIM4_CH2_60") (pintype "bidirectional"))
    )
    (net (code "101") (name "unconnected-(U4-PD14{slash}FSMC_D0{slash}TIM4_CH3-Pad61)") (class "Default")
      (node (ref "U4") (pin "61") (pinfunction "PD14/FSMC_D0/TIM4_CH3_61") (pintype "bidirectional"))
    )
    (net (code "102") (name "unconnected-(U4-PD15{slash}FSMC_D1{slash}TIM4_CH4-Pad62)") (class "Default")
      (node (ref "U4") (pin "62") (pinfunction "PD15/FSMC_D1/TIM4_CH4_62") (pintype "bidirectional"))
    )
    (net (code "103") (name "unconnected-(U4-PE2{slash}TRACECLK{slash}FSMC_A23{slash}ETH_MII_TXD3-Pad1)") (class "Default")
      (node (ref "U4") (pin "1") (pinfunction "PE2/TRACECLK/FSMC_A23/ETH_MII_TXD3_1") (pintype "bidirectional"))
    )
    (net (code "104") (name "unconnected-(U4-PE3{slash}TRACED0{slash}FSMC_A19-Pad2)") (class "Default")
      (node (ref "U4") (pin "2") (pinfunction "PE3/TRACED0/FSMC_A19_2") (pintype "bidirectional"))
    )
    (net (code "105") (name "unconnected-(U4-PE7{slash}FSMC_D4{slash}TIM1_ETR-Pad38)") (class "Default")
      (node (ref "U4") (pin "38") (pinfunction "PE7/FSMC_D4/TIM1_ETR_38") (pintype "bidirectional"))
    )
    (net (code "106") (name "unconnected-(U4-PE8{slash}FSMC_D5{slash}TIM1_CH1N-Pad39)") (class "Default")
      (node (ref "U4") (pin "39") (pinfunction "PE8/FSMC_D5/TIM1_CH1N_39") (pintype "bidirectional"))
    )
    (net (code "107") (name "unconnected-(U4-PE10{slash}FSMC_D7{slash}TIM1_CH2N-Pad41)") (class "Default")
      (node (ref "U4") (pin "41") (pinfunction "PE10/FSMC_D7/TIM1_CH2N_41") (pintype "bidirectional"))
    )
    (net (code "108") (name "unconnected-(U4-PE11{slash}FSMC_D8{slash}TIM1_CH2-Pad42)") (class "Default")
      (node (ref "U4") (pin "42") (pinfunction "PE11/FSMC_D8/TIM1_CH2_42") (pintype "bidirectional"))
    )
    (net (code "109") (name "unconnected-(U4-PE12{slash}FSMC_D9{slash}TIM1_CH3N-Pad43)") (class "Default")
      (node (ref "U4") (pin "43") (pinfunction "PE12/FSMC_D9/TIM1_CH3N_43") (pintype "bidirectional"))
    )
    (net (code "110") (name "unconnected-(U4-PE13{slash}FSMC_D10{slash}TIM1_CH3-Pad44)") (class "Default")
      (node (ref "U4") (pin "44") (pinfunction "PE13/FSMC_D10/TIM1_CH3_44") (pintype "bidirectional"))
    )
    (net (code "111") (name "unconnected-(U4-PE14{slash}FSMC_D11{slash}TIM1_CH4-Pad45)") (class "Default")
      (node (ref "U4") (pin "45") (pinfunction "PE14/FSMC_D11/TIM1_CH4_45") (pintype "bidirectional"))
    )
    (net (code "112") (name "unconnected-(U4-PE15FSMC_D12{slash}TIM1_BKIN-Pad46)") (class "Default")
      (node (ref "U4") (pin "46") (pinfunction "PE15FSMC_D12/TIM1_BKIN_46") (pintype "bidirectional"))
    )
    (net (code "113") (name "unconnected-(U8-BP-Pad4)") (class "Default")
      (node (ref "U8") (pin "4") (pinfunction "BP_4") (pintype "input"))
    )
  )
)
